# 06.net
KiCad netlist of a schematic drawn in Altium Designer
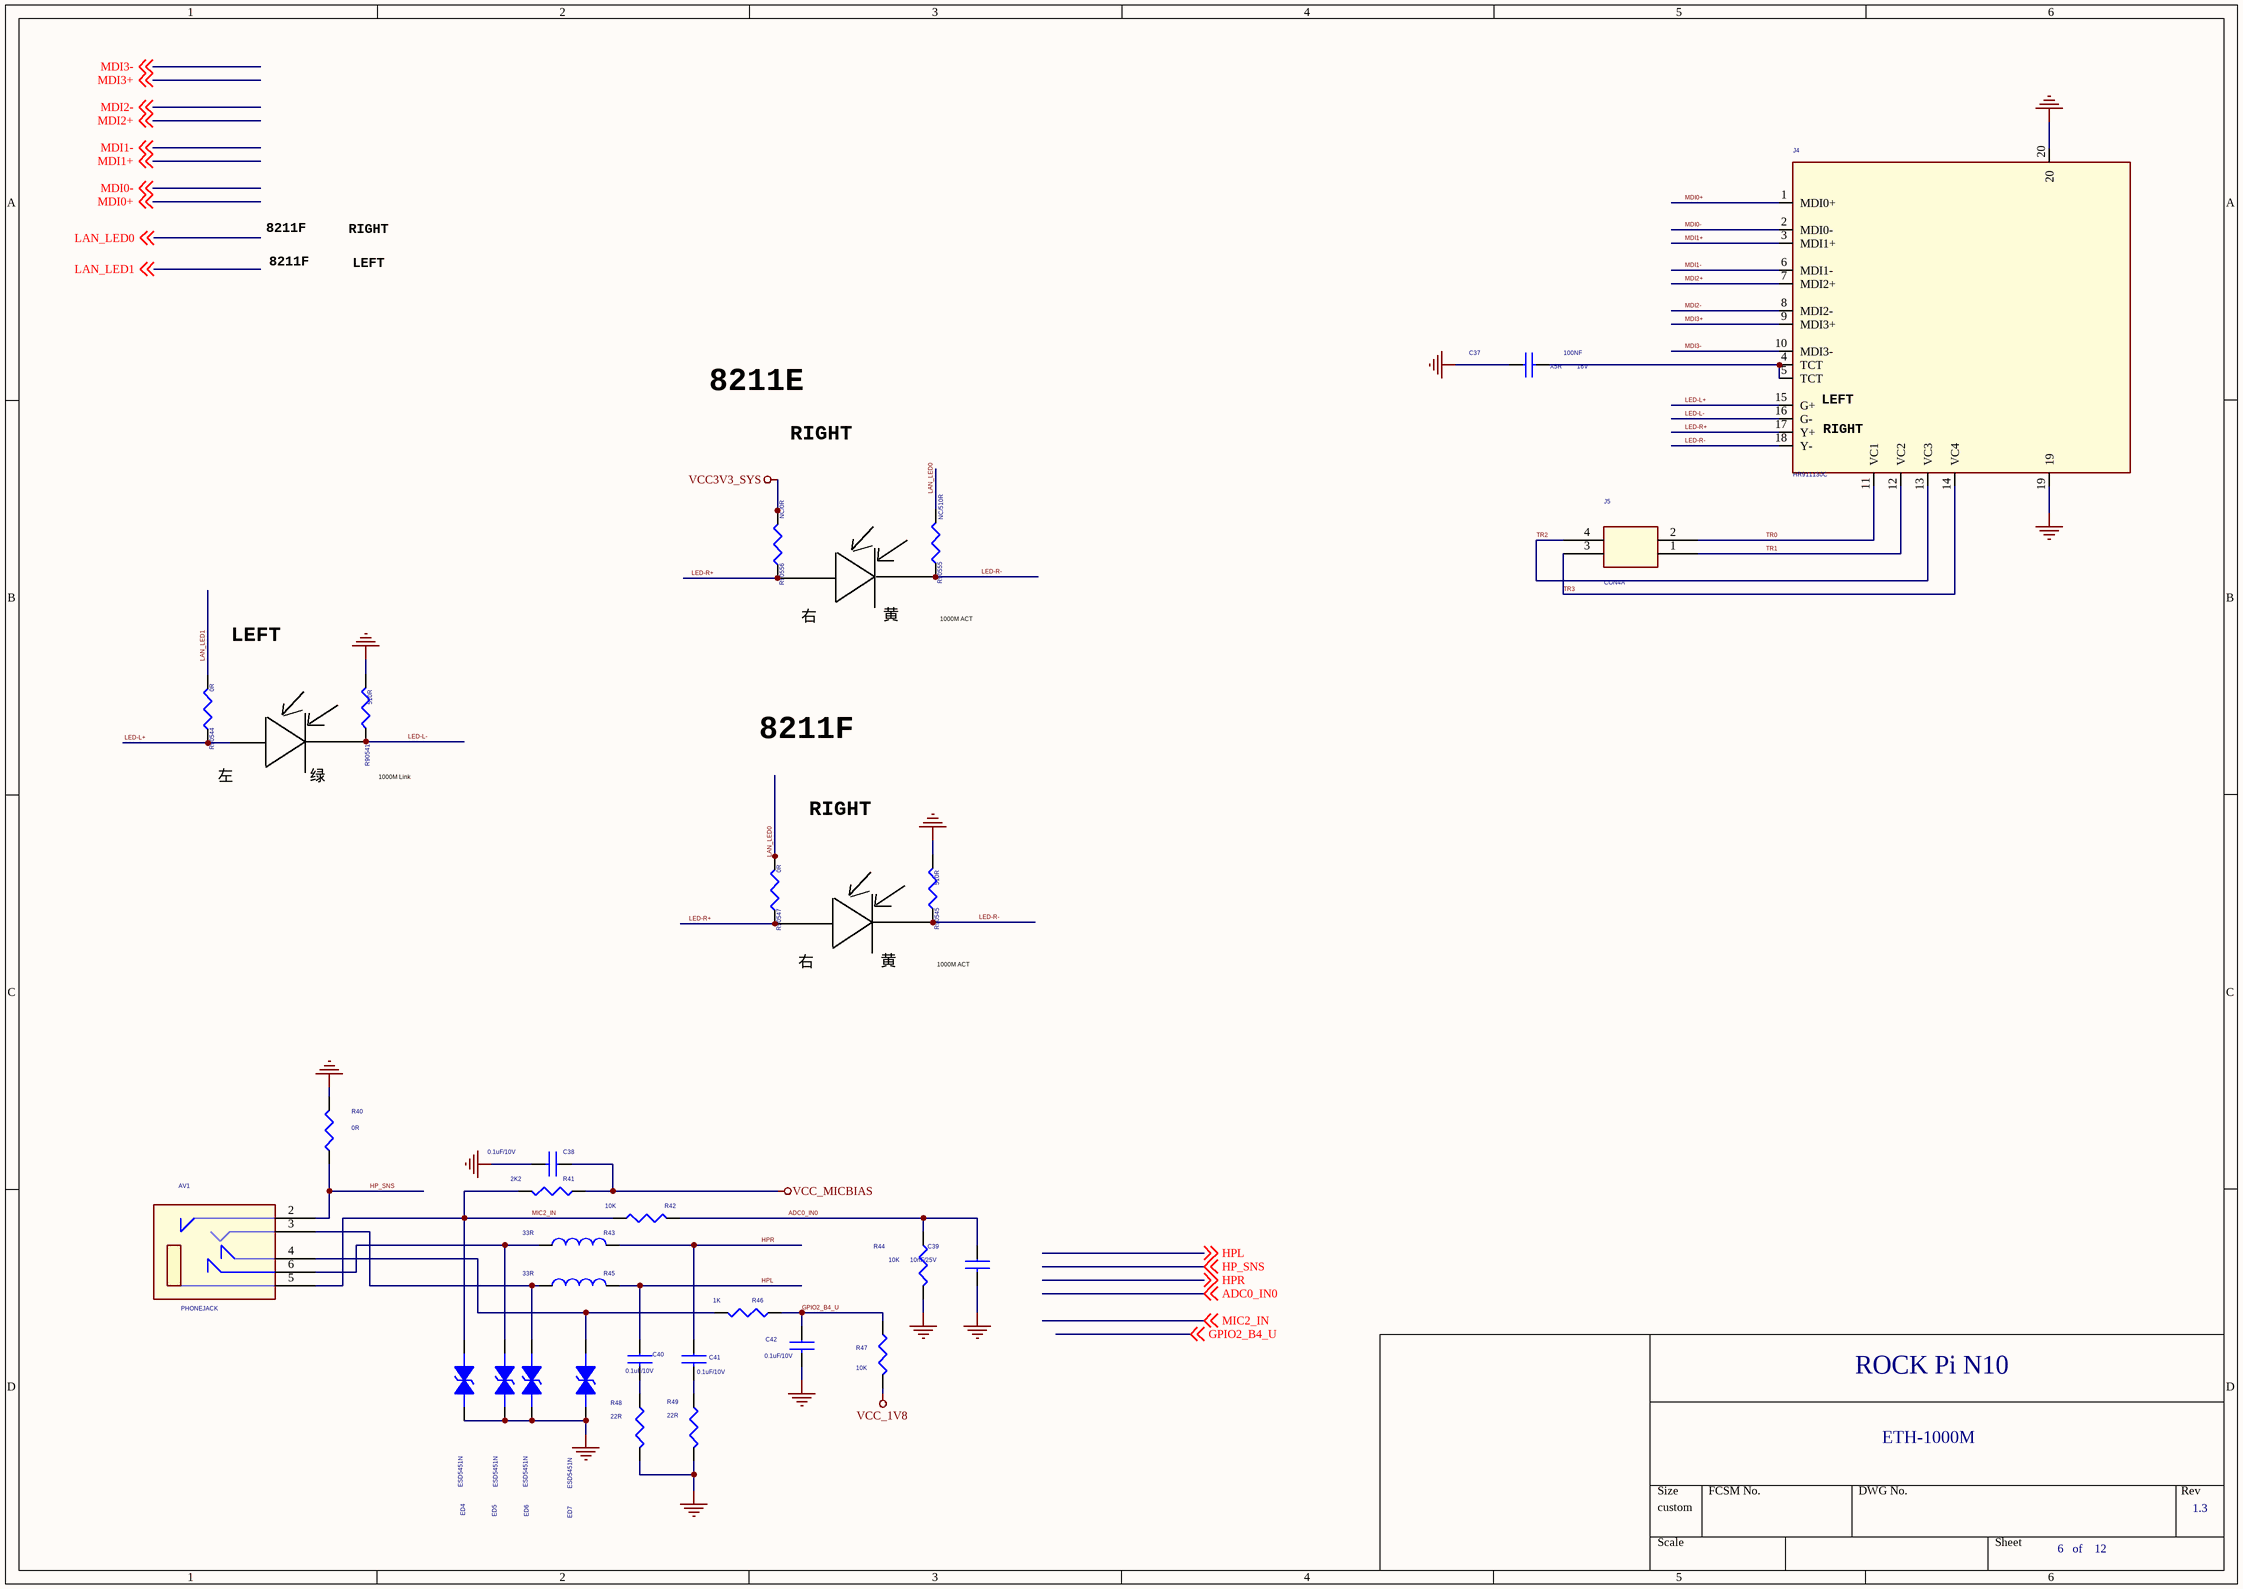
[diagram p0: 06.SchDoc]

(export (version "E")
  (design (tool "Eeschema 10.0.6"))
  (components
    (comp (ref "AV1")
      (value "PHONEJACK")
      (footprint "PJ-327A")
      (description "耳插")
      (libsource (lib "*") (part "PHONEJACK STEREO SW_3"))
    )
    (comp (ref "C37")
      (value "100NF")
      (footprint "C0805")
      (description "cap,100.00nF,+/-10%,16V,X5R,C0402")
      (fields
        (field (name "DIELECTRIC") "X5R")
        (field (name "VOLTAGE") "16V")
        (field (name "MANUFACTURER") "TDK")
        (field (name "TOLERANCE") "10%")
        (field (name "CREATED BY") "JJJ")
      )
      (libsource (lib "*") (part "CAP NP_2"))
    )
    (comp (ref "C38")
      (value "0.1uF/10V")
      (footprint "C0402")
      (description "RoHS CHIP CAP 0.1uF +10/-10% X7R")
      (libsource (lib "*") (part "CAP"))
    )
    (comp (ref "C39")
      (value "10nF/25V")
      (footprint "C0402")
      (description "RoHS CHIP CAP 0.01uF +10/-10% X7R")
      (libsource (lib "*") (part "CAP"))
    )
    (comp (ref "C40")
      (value "0.1uF/10V")
      (footprint "C0402")
      (description "RoHS CHIP CAP 0.1uF +10/-10% X7R")
      (libsource (lib "*") (part "CAP"))
    )
    (comp (ref "C41")
      (value "0.1uF/10V")
      (footprint "C0402")
      (description "RoHS CHIP CAP 0.1uF +10/-10% X7R")
      (libsource (lib "*") (part "CAP"))
    )
    (comp (ref "C42")
      (value "0.1uF/10V")
      (footprint "C0402")
      (description "RoHS CHIP CAP 0.1uF +10/-10% X7R")
      (libsource (lib "*") (part "CAP"))
    )
    (comp (ref "ED4")
      (value "ESD5451N")
      (footprint "E0402N")
      (description "ESD Component,5V,30P,SMD,0402")
      (libsource (lib "*") (part "TVS"))
    )
    (comp (ref "ED5")
      (value "ESD5451N")
      (footprint "E0402N")
      (description "ESD Component,5V,30P,SMD,0402")
      (libsource (lib "*") (part "TVS"))
    )
    (comp (ref "ED6")
      (value "ESD5451N")
      (footprint "E0402N")
      (description "ESD Component,5V,30P,SMD,0402")
      (libsource (lib "*") (part "TVS"))
    )
    (comp (ref "ED7")
      (value "ESD5451N")
      (footprint "E0402N")
      (description "ESD Component,5V,30P,SMD,0402")
      (libsource (lib "*") (part "TVS"))
    )
    (comp (ref "J4")
      (value "HR911130C")
      (footprint "RJ45_PULSE")
      (description "千兆网口接口，内置变压器")
      (fields (field (name "CREATED BY") "JJJ"))
      (libsource (lib "*") (part "HR911130C_0"))
    )
    (comp (ref "J5") (value "CON4A") (footprint "DIP4-2.54MM-2X2_FX") (libsource (lib "*") (part "CON4A_0")))
    (comp (ref "R40")
      (value "0R")
      (footprint "R0402")
      (description "ROHS CHIP RES 0R 1/16W 5%")
      (libsource (lib "*") (part "RESISTOR"))
    )
    (comp (ref "R41")
      (value "2K2")
      (footprint "R0402")
      (description "ROHS CHIP RES 2K2 1/16W 5%")
      (libsource (lib "*") (part "RESISTOR"))
    )
    (comp (ref "R42")
      (value "10K")
      (footprint "R0402")
      (description "ROHS CHIP RES 0R 1/16W 5%")
      (libsource (lib "*") (part "RESISTOR"))
    )
    (comp (ref "R43")
      (value "33R")
      (footprint "L0603")
      (description "ROHS CHIP RES 33R 1/16W 5%")
      (libsource (lib "*") (part "INDUCTOR"))
    )
    (comp (ref "R44")
      (value "10K")
      (footprint "R0402")
      (description "ROHS CHIP RES 0R 1/16W 5%")
      (libsource (lib "*") (part "RESISTOR"))
    )
    (comp (ref "R45")
      (value "33R")
      (footprint "L0603")
      (description "ROHS CHIP RES 33R 1/16W 5%")
      (libsource (lib "*") (part "INDUCTOR"))
    )
    (comp (ref "R46")
      (value "1K")
      (footprint "R0402")
      (description "ROHS CHIP RES 1K 1/16W 5%")
      (libsource (lib "*") (part "RESISTOR"))
    )
    (comp (ref "R47")
      (value "10K")
      (footprint "R0402")
      (description "ROHS CHIP RES 1K 1/16W 5%")
      (libsource (lib "*") (part "RESISTOR"))
    )
    (comp (ref "R48")
      (value "22R")
      (footprint "R0402")
      (description "ROHS CHIP RES 22R 1/16W 5%")
      (libsource (lib "*") (part "RESISTOR"))
    )
    (comp (ref "R49")
      (value "22R")
      (footprint "R0402")
      (description "ROHS CHIP RES 22R 1/16W 5%")
      (libsource (lib "*") (part "RESISTOR"))
    )
    (comp (ref "R90541")
      (value "510R")
      (footprint "R0402")
      (description "通用厚膜电阻,4K7,+/-5%,R0402,1/16W.")
      (fields
        (field (name "TOLERANCE") "5%")
        (field (name "MANUFACTURER") "YAGEO")
        (field (name "CREATED BY") "YTL")
      )
      (libsource (lib "*") (part "RESISTOR_2"))
    )
    (comp (ref "R90544")
      (value "0R")
      (footprint "R0402")
      (description "通用厚膜电阻,4K7,+/-5%,R0402,1/16W.")
      (fields
        (field (name "TOLERANCE") "5%")
        (field (name "MANUFACTURER") "YAGEO")
        (field (name "CREATED BY") "YTL")
      )
      (libsource (lib "*") (part "RESISTOR_2"))
    )
    (comp (ref "R90545")
      (value "510R")
      (footprint "R0402")
      (description "通用厚膜电阻,4K7,+/-5%,R0402,1/16W.")
      (fields
        (field (name "TOLERANCE") "5%")
        (field (name "MANUFACTURER") "YAGEO")
        (field (name "CREATED BY") "YTL")
      )
      (libsource (lib "*") (part "RESISTOR_2"))
    )
    (comp (ref "R90547")
      (value "0R")
      (footprint "R0402")
      (description "通用厚膜电阻,4K7,+/-5%,R0402,1/16W.")
      (fields
        (field (name "TOLERANCE") "5%")
        (field (name "MANUFACTURER") "YAGEO")
        (field (name "CREATED BY") "YTL")
      )
      (libsource (lib "*") (part "RESISTOR_2"))
    )
    (comp (ref "R90555")
      (value "NC/510R")
      (footprint "R0402")
      (description "通用厚膜电阻,4K7,+/-5%,R0402,1/16W.")
      (fields
        (field (name "TOLERANCE") "5%")
        (field (name "MANUFACTURER") "YAGEO")
        (field (name "CREATED BY") "YTL")
      )
      (libsource (lib "*") (part "RESISTOR_2"))
    )
    (comp (ref "R90556")
      (value "NC/0R")
      (footprint "R0402")
      (description "通用厚膜电阻,4K7,+/-5%,R0402,1/16W.")
      (fields
        (field (name "TOLERANCE") "5%")
        (field (name "MANUFACTURER") "YAGEO")
        (field (name "CREATED BY") "YTL")
      )
      (libsource (lib "*") (part "RESISTOR_2"))
    )
  )
  (nets
    (net (code "1") (name "/LED-L+") (class "Default")
      (node (ref "J4") (pin "15") (pinfunction "G+_15") (pintype "passive"))
      (node (ref "R90544") (pin "1") (pinfunction "1_1") (pintype "passive"))
    )
    (net (code "2") (name "/LED-L-") (class "Default")
      (node (ref "J4") (pin "16") (pinfunction "G-_16") (pintype "passive"))
      (node (ref "R90541") (pin "1") (pinfunction "1_1") (pintype "passive"))
    )
    (net (code "3") (name "/LED-R+") (class "Default")
      (node (ref "J4") (pin "17") (pinfunction "Y+_17") (pintype "passive"))
      (node (ref "R90547") (pin "1") (pinfunction "1_1") (pintype "passive"))
      (node (ref "R90556") (pin "1") (pinfunction "1_1") (pintype "passive"))
    )
    (net (code "4") (name "/LED-R-") (class "Default")
      (node (ref "J4") (pin "18") (pinfunction "Y-_18") (pintype "passive"))
      (node (ref "R90545") (pin "1") (pinfunction "1_1") (pintype "passive"))
      (node (ref "R90555") (pin "1") (pinfunction "1_1") (pintype "passive"))
    )
    (net (code "5") (name "/TR0") (class "Default")
      (node (ref "J4") (pin "11") (pinfunction "VC1_11") (pintype "passive"))
      (node (ref "J5") (pin "2") (pinfunction "2_2") (pintype "passive"))
    )
    (net (code "6") (name "/TR1") (class "Default")
      (node (ref "J4") (pin "12") (pinfunction "VC2_12") (pintype "passive"))
      (node (ref "J5") (pin "1") (pinfunction "1_1") (pintype "passive"))
    )
    (net (code "7") (name "/TR2") (class "Default")
      (node (ref "J4") (pin "13") (pinfunction "VC3_13") (pintype "passive"))
      (node (ref "J5") (pin "4") (pinfunction "4_4") (pintype "passive"))
    )
    (net (code "8") (name "/TR3") (class "Default")
      (node (ref "J4") (pin "14") (pinfunction "VC4_14") (pintype "passive"))
      (node (ref "J5") (pin "3") (pinfunction "3_3") (pintype "passive"))
    )
    (net (code "9") (name "ADC0_IN0") (class "Default")
      (node (ref "C39") (pin "1") (pinfunction "1_1") (pintype "passive"))
      (node (ref "R42") (pin "1") (pinfunction "1_1") (pintype "passive"))
      (node (ref "R44") (pin "2") (pinfunction "2_2") (pintype "passive"))
    )
    (net (code "10") (name "GND") (class "Default")
      (node (ref "C37") (pin "1") (pinfunction "1_1") (pintype "passive"))
      (node (ref "C38") (pin "2") (pinfunction "2_2") (pintype "passive"))
      (node (ref "C39") (pin "2") (pinfunction "2_2") (pintype "passive"))
      (node (ref "C42") (pin "2") (pinfunction "2_2") (pintype "passive"))
      (node (ref "ED4") (pin "2") (pinfunction "2_2") (pintype "passive"))
      (node (ref "ED5") (pin "2") (pinfunction "2_2") (pintype "passive"))
      (node (ref "ED6") (pin "2") (pinfunction "2_2") (pintype "passive"))
      (node (ref "ED7") (pin "2") (pinfunction "2_2") (pintype "passive"))
      (node (ref "J4") (pin "19") (pinfunction "19_19") (pintype "passive"))
      (node (ref "J4") (pin "20") (pinfunction "20_20") (pintype "passive"))
      (node (ref "R40") (pin "1") (pinfunction "1_1") (pintype "passive"))
      (node (ref "R44") (pin "1") (pinfunction "1_1") (pintype "passive"))
      (node (ref "R48") (pin "1") (pinfunction "1_1") (pintype "passive"))
      (node (ref "R49") (pin "1") (pinfunction "1_1") (pintype "passive"))
      (node (ref "R90541") (pin "2") (pinfunction "2_2") (pintype "passive"))
      (node (ref "R90545") (pin "2") (pinfunction "2_2") (pintype "passive"))
    )
    (net (code "11") (name "GPIO2_B4_U") (class "Default")
      (node (ref "C42") (pin "1") (pinfunction "1_1") (pintype "passive"))
      (node (ref "R46") (pin "2") (pinfunction "2_2") (pintype "passive"))
      (node (ref "R47") (pin "2") (pinfunction "2_2") (pintype "passive"))
    )
    (net (code "12") (name "HPL") (class "Default")
      (node (ref "C40") (pin "1") (pinfunction "1_1") (pintype "passive"))
      (node (ref "R45") (pin "2") (pinfunction "2_2") (pintype "passive"))
    )
    (net (code "13") (name "HPR") (class "Default")
      (node (ref "C41") (pin "1") (pinfunction "1_1") (pintype "passive"))
      (node (ref "R43") (pin "2") (pinfunction "2_2") (pintype "passive"))
    )
    (net (code "14") (name "HP_SNS") (class "Default")
      (node (ref "AV1") (pin "2") (pinfunction "DH_2") (pintype "passive"))
      (node (ref "R40") (pin "2") (pinfunction "2_2") (pintype "passive"))
    )
    (net (code "15") (name "LAN_LED0") (class "Default")
      (node (ref "R90547") (pin "2") (pinfunction "2_2") (pintype "passive"))
      (node (ref "R90555") (pin "2") (pinfunction "2_2") (pintype "passive"))
    )
    (net (code "16") (name "LAN_LED1") (class "Default")
      (node (ref "R90544") (pin "2") (pinfunction "2_2") (pintype "passive"))
    )
    (net (code "17") (name "MDI0+") (class "Default")
      (node (ref "J4") (pin "1") (pinfunction "MDI0+_1") (pintype "passive"))
    )
    (net (code "18") (name "MDI0-") (class "Default")
      (node (ref "J4") (pin "2") (pinfunction "MDI0-_2") (pintype "passive"))
    )
    (net (code "19") (name "MDI1+") (class "Default")
      (node (ref "J4") (pin "3") (pinfunction "MDI1+_3") (pintype "passive"))
    )
    (net (code "20") (name "MDI1-") (class "Default")
      (node (ref "J4") (pin "6") (pinfunction "MDI1-_6") (pintype "passive"))
    )
    (net (code "21") (name "MDI2+") (class "Default")
      (node (ref "J4") (pin "7") (pinfunction "MDI2+_7") (pintype "passive"))
    )
    (net (code "22") (name "MDI2-") (class "Default")
      (node (ref "J4") (pin "8") (pinfunction "MDI2-_8") (pintype "passive"))
    )
    (net (code "23") (name "MDI3+") (class "Default")
      (node (ref "J4") (pin "9") (pinfunction "MDI3+_9") (pintype "passive"))
    )
    (net (code "24") (name "MDI3-") (class "Default")
      (node (ref "J4") (pin "10") (pinfunction "MDI3-_10") (pintype "passive"))
    )
    (net (code "25") (name "MIC2_IN") (class "Default")
      (node (ref "AV1") (pin "5") (pinfunction "D_5") (pintype "passive"))
      (node (ref "ED4") (pin "1") (pinfunction "1_1") (pintype "passive"))
      (node (ref "R41") (pin "1") (pinfunction "1_1") (pintype "passive"))
      (node (ref "R42") (pin "2") (pinfunction "2_2") (pintype "passive"))
    )
    (net (code "26") (name "Net-(AV1-HP)") (class "Default")
      (node (ref "AV1") (pin "6") (pinfunction "HP_6") (pintype "passive"))
      (node (ref "ED5") (pin "1") (pinfunction "1_1") (pintype "passive"))
      (node (ref "R43") (pin "1") (pinfunction "1_1") (pintype "passive"))
    )
    (net (code "27") (name "Net-(AV1-L)") (class "Default")
      (node (ref "AV1") (pin "4") (pinfunction "L_4") (pintype "passive"))
      (node (ref "ED7") (pin "1") (pinfunction "1_1") (pintype "passive"))
      (node (ref "R46") (pin "1") (pinfunction "1_1") (pintype "passive"))
    )
    (net (code "28") (name "Net-(AV1-R)") (class "Default")
      (node (ref "AV1") (pin "3") (pinfunction "R_3") (pintype "passive"))
      (node (ref "ED6") (pin "1") (pinfunction "1_1") (pintype "passive"))
      (node (ref "R45") (pin "1") (pinfunction "1_1") (pintype "passive"))
    )
    (net (code "29") (name "Net-(C37-Pad2)") (class "Default")
      (node (ref "C37") (pin "2") (pinfunction "2_2") (pintype "passive"))
      (node (ref "J4") (pin "4") (pinfunction "TCT_4") (pintype "passive"))
      (node (ref "J4") (pin "5") (pinfunction "TCT_5") (pintype "passive"))
    )
    (net (code "30") (name "Net-(C40-Pad2)") (class "Default")
      (node (ref "C40") (pin "2") (pinfunction "2_2") (pintype "passive"))
      (node (ref "R48") (pin "2") (pinfunction "2_2") (pintype "passive"))
    )
    (net (code "31") (name "Net-(C41-Pad2)") (class "Default")
      (node (ref "C41") (pin "2") (pinfunction "2_2") (pintype "passive"))
      (node (ref "R49") (pin "2") (pinfunction "2_2") (pintype "passive"))
    )
    (net (code "32") (name "VCC3V3_SYS") (class "Default")
      (node (ref "R90556") (pin "2") (pinfunction "2_2") (pintype "passive"))
    )
    (net (code "33") (name "VCC_1V8") (class "Default")
      (node (ref "R47") (pin "1") (pinfunction "1_1") (pintype "passive"))
    )
    (net (code "34") (name "VCC_MICBIAS") (class "Default")
      (node (ref "C38") (pin "1") (pinfunction "1_1") (pintype "passive"))
      (node (ref "R41") (pin "2") (pinfunction "2_2") (pintype "passive"))
    )
  )
)
